# Flash.net
KiCad netlist of a schematic drawn in Altium Designer
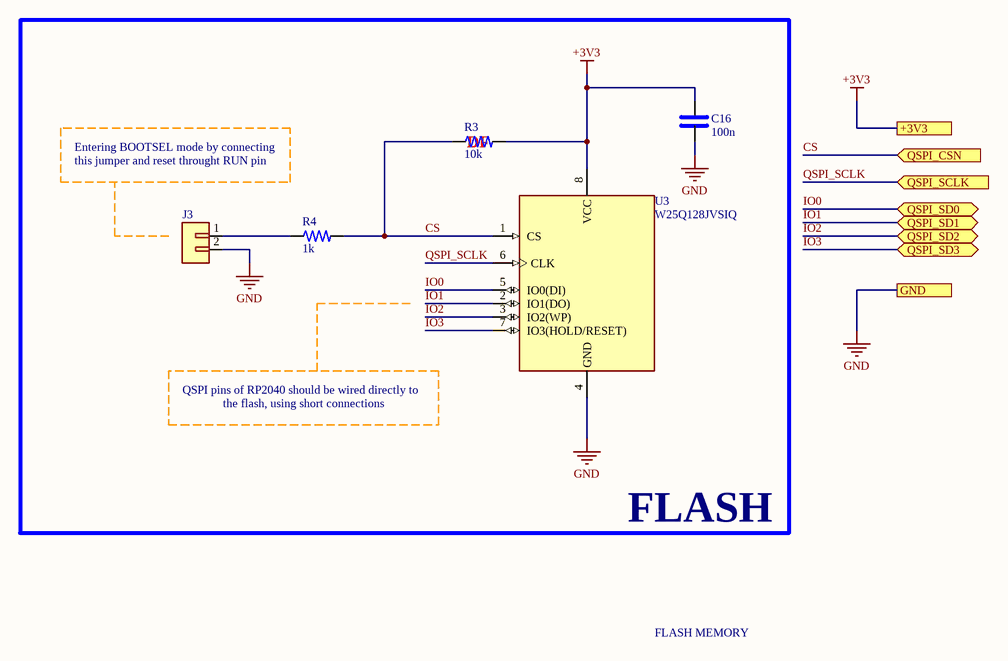
[diagram p0: Flash.SchDoc]

(export (version "E")
  (design (tool "Eeschema 10.0.6"))
  (components
    (comp (ref "C16")
      (value "100n")
      (footprint "0402 CAP")
      (fields
        (field (name "MANUFACTURER") "KEMET")
        (field (name "MANUFACTURER PART NUMBER") "C0805C104K4RACTU")
      )
      (libsource (lib "Integrated_Library") (part "0402 SMD Capacitor"))
    )
    (comp (ref "J3")
      (value "2 Position male pin header")
      (footprint "SAMTEC-TMM-101-03-X-D")
      (libsource (lib "Integrated_Library") (part "SAMTEC-TMM-101-03-X-D"))
    )
    (comp (ref "R3")
      (value "10k")
      (footprint "0402 RES")
      (fields
        (field (name "MANUFACTURER") "Yageo")
        (field (name "MANUFACTURER PART NUMBER") "SR0805KR-0710KL")
      )
      (libsource (lib "Integrated_Library") (part "0402 SMD Resistor"))
    )
    (comp (ref "R4")
      (value "1k")
      (footprint "0402 RES")
      (fields
        (field (name "MANUFACTURER") "Yageo")
        (field (name "MANUFACTURER PART NUMBER") "RC0805FR-071KL")
        (field (name "POWER") "125mW")
      )
      (libsource (lib "Integrated_Library") (part "0402 SMD Resistor"))
    )
    (comp (ref "U3")
      (value "W25Q128JVSIQ")
      (footprint "SOIC127P790X216-8N")
      (description "FLASH - NOR Memory IC 128Mb (16M x 8) SPI - Quad I/O, QPI, DTR 133 MHz 8-SOIC")
      (fields (field (name "MF") "Winbond Electronics"))
      (libsource (lib "Integrated_Library") (part "W25Q128JVSIQ"))
    )
  )
  (nets
    (net (code "1") (name "+3V3") (class "Default")
      (node (ref "C16") (pin "2") (pinfunction "2_2") (pintype "passive"))
      (node (ref "R3") (pin "2") (pinfunction "2_2") (pintype "passive"))
      (node (ref "U3") (pin "8") (pinfunction "VCC_8") (pintype "power_in"))
    )
    (net (code "2") (name "/CS") (class "Default")
      (node (ref "R3") (pin "1") (pinfunction "1_1") (pintype "passive"))
      (node (ref "R4") (pin "2") (pinfunction "2_2") (pintype "passive"))
      (node (ref "U3") (pin "1") (pinfunction "CS_1") (pintype "input"))
    )
    (net (code "3") (name "/IO0") (class "Default")
      (node (ref "U3") (pin "5") (pinfunction "IO0(DI)_5") (pintype "bidirectional"))
    )
    (net (code "4") (name "/IO1") (class "Default")
      (node (ref "U3") (pin "2") (pinfunction "IO1(DO)_2") (pintype "bidirectional"))
    )
    (net (code "5") (name "/IO2") (class "Default")
      (node (ref "U3") (pin "3") (pinfunction "IO2(WP)_3") (pintype "bidirectional"))
    )
    (net (code "6") (name "/IO3") (class "Default")
      (node (ref "U3") (pin "7") (pinfunction "IO3(HOLD/RESET)_7") (pintype "bidirectional"))
    )
    (net (code "7") (name "/QSPI_SCLK") (class "Default")
      (node (ref "U3") (pin "6") (pinfunction "CLK_6") (pintype "input"))
    )
    (net (code "8") (name "GND") (class "Default")
      (node (ref "C16") (pin "1") (pinfunction "1_1") (pintype "passive"))
      (node (ref "J3") (pin "2") (pinfunction "2_2") (pintype "passive"))
      (node (ref "U3") (pin "4") (pinfunction "GND_4") (pintype "power_in"))
    )
    (net (code "9") (name "Net-(J3-Pad1)") (class "Default")
      (node (ref "J3") (pin "1") (pinfunction "1_1") (pintype "passive"))
      (node (ref "R4") (pin "1") (pinfunction "1_1") (pintype "passive"))
    )
  )
)
